# sonar_hotfix_2.net
KiCad netlist of a schematic drawn in EAGLE
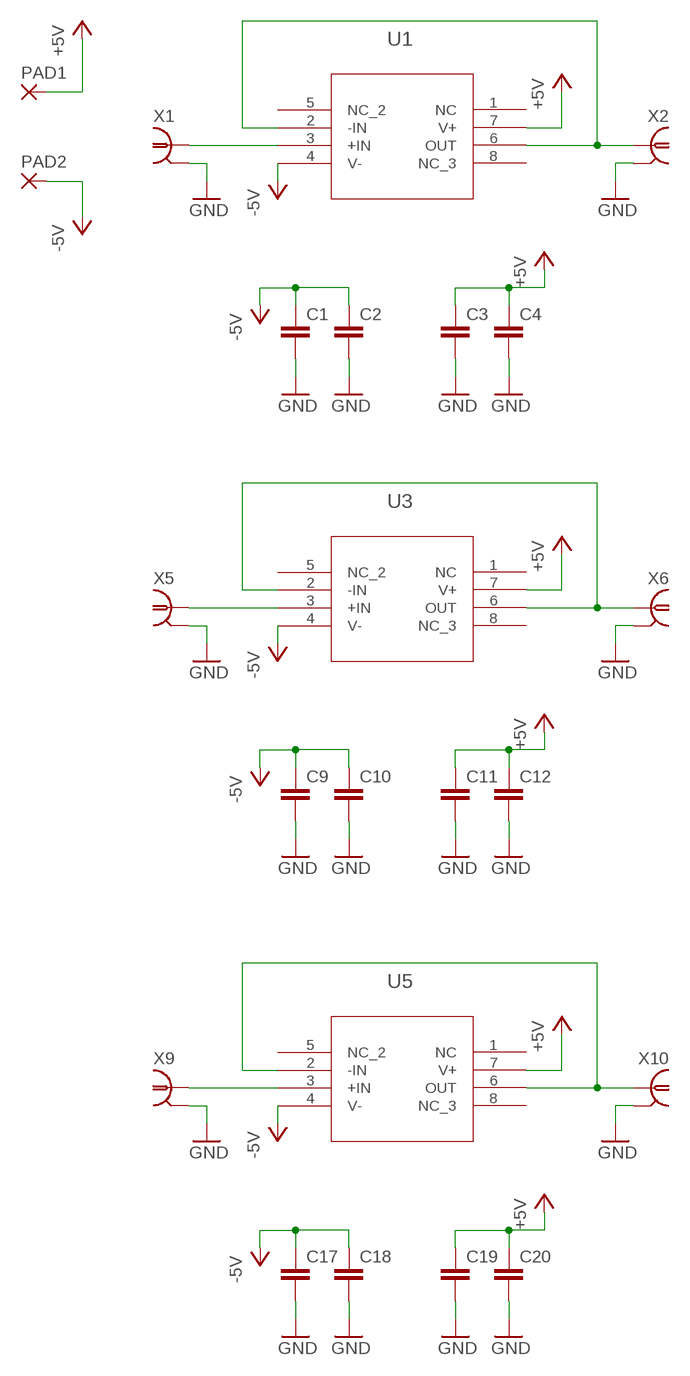
[diagram p0: schematic, sheet 1]

(export (version "E")
  (design (tool "Eeschema 10.0.6"))
  (components
    (comp (ref "C1")
      (value "C-EUC0603")
      (footprint "eagle-import:C0603")
      (libsource (lib "eagle-import") (part "C-EUC0603"))
    )
    (comp (ref "C2")
      (value "C-EUC0603")
      (footprint "eagle-import:C0603")
      (libsource (lib "eagle-import") (part "C-EUC0603"))
    )
    (comp (ref "C3")
      (value "C-EUC0603")
      (footprint "eagle-import:C0603")
      (libsource (lib "eagle-import") (part "C-EUC0603"))
    )
    (comp (ref "C4")
      (value "C-EUC0603")
      (footprint "eagle-import:C0603")
      (libsource (lib "eagle-import") (part "C-EUC0603"))
    )
    (comp (ref "C9")
      (value "C-EUC0603")
      (footprint "eagle-import:C0603")
      (libsource (lib "eagle-import") (part "C-EUC0603"))
    )
    (comp (ref "C10")
      (value "C-EUC0603")
      (footprint "eagle-import:C0603")
      (libsource (lib "eagle-import") (part "C-EUC0603"))
    )
    (comp (ref "C11")
      (value "C-EUC0603")
      (footprint "eagle-import:C0603")
      (libsource (lib "eagle-import") (part "C-EUC0603"))
    )
    (comp (ref "C12")
      (value "C-EUC0603")
      (footprint "eagle-import:C0603")
      (libsource (lib "eagle-import") (part "C-EUC0603"))
    )
    (comp (ref "C17")
      (value "C-EUC0603")
      (footprint "eagle-import:C0603")
      (libsource (lib "eagle-import") (part "C-EUC0603"))
    )
    (comp (ref "C18")
      (value "C-EUC0603")
      (footprint "eagle-import:C0603")
      (libsource (lib "eagle-import") (part "C-EUC0603"))
    )
    (comp (ref "C19")
      (value "C-EUC0603")
      (footprint "eagle-import:C0603")
      (libsource (lib "eagle-import") (part "C-EUC0603"))
    )
    (comp (ref "C20")
      (value "C-EUC0603")
      (footprint "eagle-import:C0603")
      (libsource (lib "eagle-import") (part "C-EUC0603"))
    )
    (comp (ref "PAD1")
      (value "WIREPADSMD5-2,5")
      (footprint "eagle-import:5-2,5")
      (libsource (lib "eagle-import") (part "WIREPADSMD5-2,5"))
    )
    (comp (ref "PAD2")
      (value "WIREPADSMD5-2,5")
      (footprint "eagle-import:5-2,5")
      (libsource (lib "eagle-import") (part "WIREPADSMD5-2,5"))
    )
    (comp (ref "U1")
      (value "LTC6240SO-8")
      (footprint "eagle-import:SO-8")
      (libsource (lib "eagle-import") (part "LTC6240SO-8"))
    )
    (comp (ref "U3")
      (value "LTC6240SO-8")
      (footprint "eagle-import:SO-8")
      (libsource (lib "eagle-import") (part "LTC6240SO-8"))
    )
    (comp (ref "U5")
      (value "LTC6240SO-8")
      (footprint "eagle-import:SO-8")
      (libsource (lib "eagle-import") (part "LTC6240SO-8"))
    )
    (comp (ref "X1")
      (value "0731000105")
      (footprint "eagle-import:0731000105")
      (libsource (lib "eagle-import") (part "0731000105"))
    )
    (comp (ref "X2")
      (value "0731000105")
      (footprint "eagle-import:0731000105")
      (libsource (lib "eagle-import") (part "0731000105"))
    )
    (comp (ref "X5")
      (value "0731000105")
      (footprint "eagle-import:0731000105")
      (libsource (lib "eagle-import") (part "0731000105"))
    )
    (comp (ref "X6")
      (value "0731000105")
      (footprint "eagle-import:0731000105")
      (libsource (lib "eagle-import") (part "0731000105"))
    )
    (comp (ref "X9")
      (value "0731000105")
      (footprint "eagle-import:0731000105")
      (libsource (lib "eagle-import") (part "0731000105"))
    )
    (comp (ref "X10")
      (value "0731000105")
      (footprint "eagle-import:0731000105")
      (libsource (lib "eagle-import") (part "0731000105"))
    )
  )
  (nets
    (net (code "1") (name "+5V") (class "Default")
      (node (ref "C11") (pin "1") (pinfunction "1_1") (pintype "passive"))
      (node (ref "C12") (pin "1") (pinfunction "1_1") (pintype "passive"))
      (node (ref "C19") (pin "1") (pinfunction "1_1") (pintype "passive"))
      (node (ref "C20") (pin "1") (pinfunction "1_1") (pintype "passive"))
      (node (ref "C3") (pin "1") (pinfunction "1_1") (pintype "passive"))
      (node (ref "C4") (pin "1") (pinfunction "1_1") (pintype "passive"))
      (node (ref "PAD1") (pin "1") (pinfunction "P_1") (pintype "passive"))
      (node (ref "U1") (pin "7") (pinfunction "V+_7") (pintype "power_in"))
      (node (ref "U3") (pin "7") (pinfunction "V+_7") (pintype "power_in"))
      (node (ref "U5") (pin "7") (pinfunction "V+_7") (pintype "power_in"))
    )
    (net (code "2") (name "-5V") (class "Default")
      (node (ref "C1") (pin "1") (pinfunction "1_1") (pintype "passive"))
      (node (ref "C10") (pin "1") (pinfunction "1_1") (pintype "passive"))
      (node (ref "C17") (pin "1") (pinfunction "1_1") (pintype "passive"))
      (node (ref "C18") (pin "1") (pinfunction "1_1") (pintype "passive"))
      (node (ref "C2") (pin "1") (pinfunction "1_1") (pintype "passive"))
      (node (ref "C9") (pin "1") (pinfunction "1_1") (pintype "passive"))
      (node (ref "PAD2") (pin "1") (pinfunction "P_1") (pintype "passive"))
      (node (ref "U1") (pin "4") (pinfunction "V-_4") (pintype "power_in"))
      (node (ref "U3") (pin "4") (pinfunction "V-_4") (pintype "power_in"))
      (node (ref "U5") (pin "4") (pinfunction "V-_4") (pintype "power_in"))
    )
    (net (code "3") (name "GND") (class "Default")
      (node (ref "C1") (pin "2") (pinfunction "2_2") (pintype "passive"))
      (node (ref "C10") (pin "2") (pinfunction "2_2") (pintype "passive"))
      (node (ref "C11") (pin "2") (pinfunction "2_2") (pintype "passive"))
      (node (ref "C12") (pin "2") (pinfunction "2_2") (pintype "passive"))
      (node (ref "C17") (pin "2") (pinfunction "2_2") (pintype "passive"))
      (node (ref "C18") (pin "2") (pinfunction "2_2") (pintype "passive"))
      (node (ref "C19") (pin "2") (pinfunction "2_2") (pintype "passive"))
      (node (ref "C2") (pin "2") (pinfunction "2_2") (pintype "passive"))
      (node (ref "C20") (pin "2") (pinfunction "2_2") (pintype "passive"))
      (node (ref "C3") (pin "2") (pinfunction "2_2") (pintype "passive"))
      (node (ref "C4") (pin "2") (pinfunction "2_2") (pintype "passive"))
      (node (ref "C9") (pin "2") (pinfunction "2_2") (pintype "passive"))
      (node (ref "X1") (pin "P$1") (pinfunction "2_P$1") (pintype "passive"))
      (node (ref "X1") (pin "P$2") (pinfunction "2_P$2") (pintype "passive"))
      (node (ref "X10") (pin "P$1") (pinfunction "2_P$1") (pintype "passive"))
      (node (ref "X10") (pin "P$2") (pinfunction "2_P$2") (pintype "passive"))
      (node (ref "X2") (pin "P$1") (pinfunction "2_P$1") (pintype "passive"))
      (node (ref "X2") (pin "P$2") (pinfunction "2_P$2") (pintype "passive"))
      (node (ref "X5") (pin "P$1") (pinfunction "2_P$1") (pintype "passive"))
      (node (ref "X5") (pin "P$2") (pinfunction "2_P$2") (pintype "passive"))
      (node (ref "X6") (pin "P$1") (pinfunction "2_P$1") (pintype "passive"))
      (node (ref "X6") (pin "P$2") (pinfunction "2_P$2") (pintype "passive"))
      (node (ref "X9") (pin "P$1") (pinfunction "2_P$1") (pintype "passive"))
      (node (ref "X9") (pin "P$2") (pinfunction "2_P$2") (pintype "passive"))
    )
    (net (code "4") (name "Net-(U1-+IN)") (class "Default")
      (node (ref "U1") (pin "3") (pinfunction "+IN_3") (pintype "input"))
      (node (ref "X1") (pin "P$3") (pinfunction "1_P$3") (pintype "passive"))
    )
    (net (code "5") (name "Net-(U1--IN)") (class "Default")
      (node (ref "U1") (pin "2") (pinfunction "-IN_2") (pintype "input"))
      (node (ref "U1") (pin "6") (pinfunction "OUT_6") (pintype "output"))
      (node (ref "X2") (pin "P$3") (pinfunction "1_P$3") (pintype "passive"))
    )
    (net (code "6") (name "Net-(U3-+IN)") (class "Default")
      (node (ref "U3") (pin "3") (pinfunction "+IN_3") (pintype "input"))
      (node (ref "X5") (pin "P$3") (pinfunction "1_P$3") (pintype "passive"))
    )
    (net (code "7") (name "Net-(U3--IN)") (class "Default")
      (node (ref "U3") (pin "2") (pinfunction "-IN_2") (pintype "input"))
      (node (ref "U3") (pin "6") (pinfunction "OUT_6") (pintype "output"))
      (node (ref "X6") (pin "P$3") (pinfunction "1_P$3") (pintype "passive"))
    )
    (net (code "8") (name "Net-(U5-+IN)") (class "Default")
      (node (ref "U5") (pin "3") (pinfunction "+IN_3") (pintype "input"))
      (node (ref "X9") (pin "P$3") (pinfunction "1_P$3") (pintype "passive"))
    )
    (net (code "9") (name "Net-(U5--IN)") (class "Default")
      (node (ref "U5") (pin "2") (pinfunction "-IN_2") (pintype "input"))
      (node (ref "U5") (pin "6") (pinfunction "OUT_6") (pintype "output"))
      (node (ref "X10") (pin "P$3") (pinfunction "1_P$3") (pintype "passive"))
    )
    (net (code "10") (name "unconnected-(U1-NC-Pad1)") (class "Default")
      (node (ref "U1") (pin "1") (pinfunction "NC_1") (pintype "no_connect"))
    )
    (net (code "11") (name "unconnected-(U1-NC_2-Pad5)") (class "Default")
      (node (ref "U1") (pin "5") (pinfunction "NC_2_5") (pintype "no_connect"))
    )
    (net (code "12") (name "unconnected-(U1-NC_3-Pad8)") (class "Default")
      (node (ref "U1") (pin "8") (pinfunction "NC_3_8") (pintype "no_connect"))
    )
    (net (code "13") (name "unconnected-(U3-NC-Pad1)") (class "Default")
      (node (ref "U3") (pin "1") (pinfunction "NC_1") (pintype "no_connect"))
    )
    (net (code "14") (name "unconnected-(U3-NC_2-Pad5)") (class "Default")
      (node (ref "U3") (pin "5") (pinfunction "NC_2_5") (pintype "no_connect"))
    )
    (net (code "15") (name "unconnected-(U3-NC_3-Pad8)") (class "Default")
      (node (ref "U3") (pin "8") (pinfunction "NC_3_8") (pintype "no_connect"))
    )
    (net (code "16") (name "unconnected-(U5-NC-Pad1)") (class "Default")
      (node (ref "U5") (pin "1") (pinfunction "NC_1") (pintype "no_connect"))
    )
    (net (code "17") (name "unconnected-(U5-NC_2-Pad5)") (class "Default")
      (node (ref "U5") (pin "5") (pinfunction "NC_2_5") (pintype "no_connect"))
    )
    (net (code "18") (name "unconnected-(U5-NC_3-Pad8)") (class "Default")
      (node (ref "U5") (pin "8") (pinfunction "NC_3_8") (pintype "no_connect"))
    )
  )
)
